# 2015_FDP_SCHEMA.net
KiCad netlist of a schematic drawn in Altium Designer
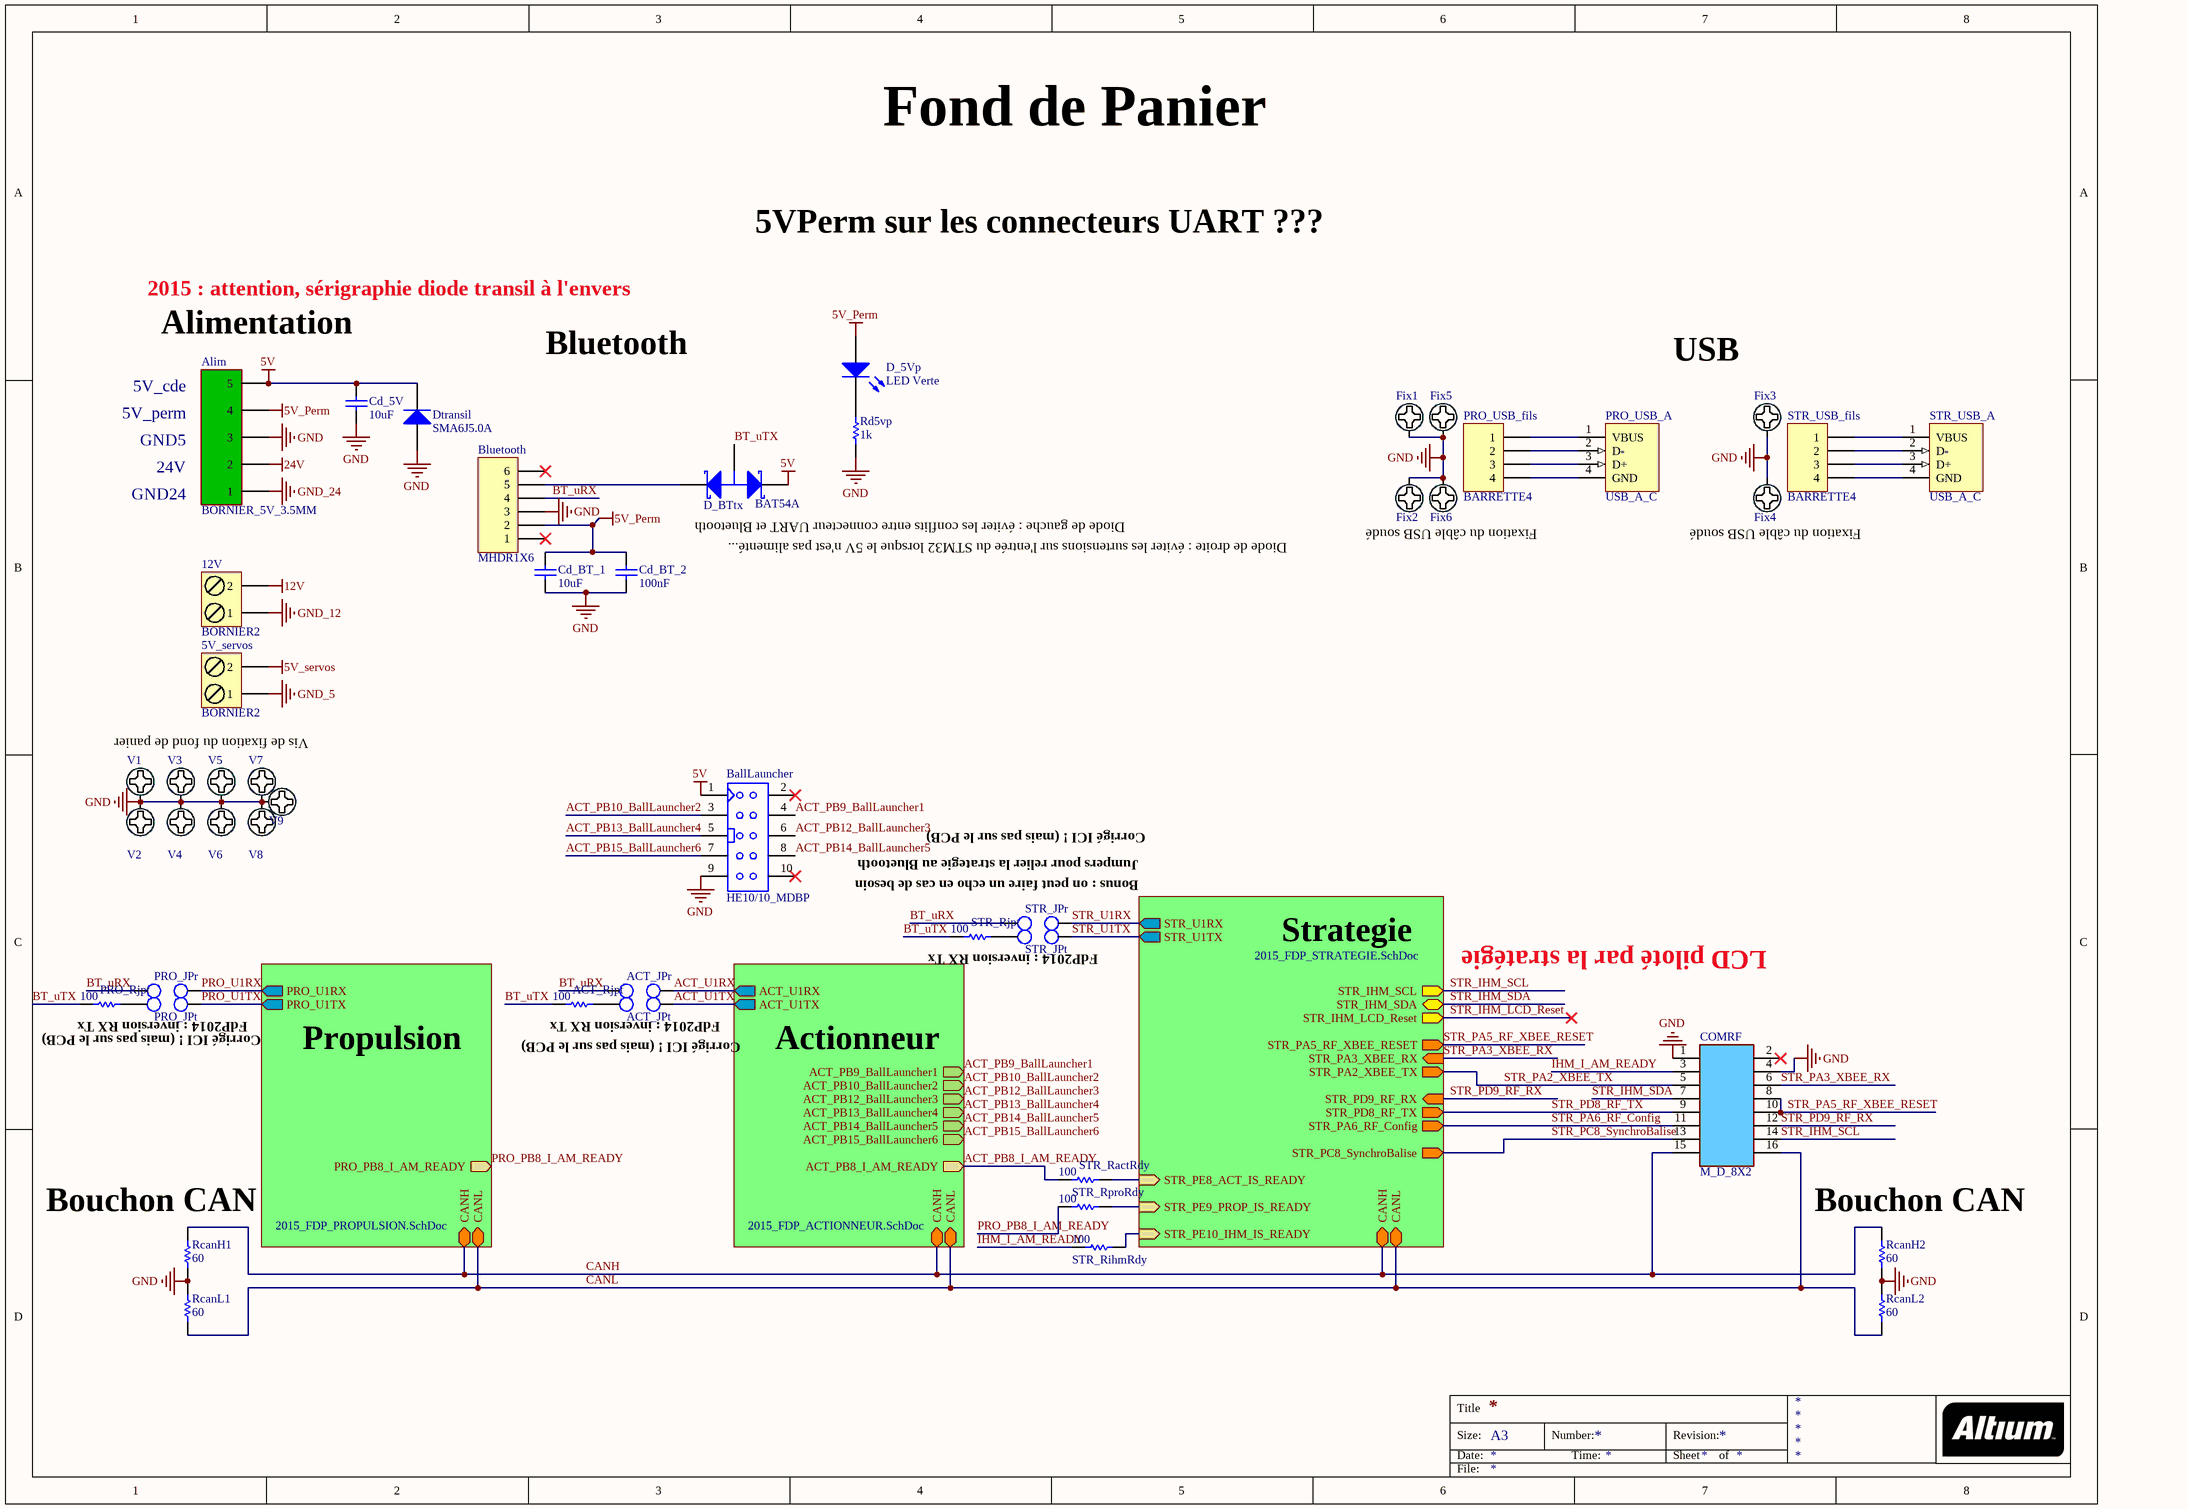
[diagram p0: 2015_FDP_SCHEMA.SchDoc]

(export (version "E")
  (design (tool "Eeschema 10.0.6"))
  (components
    (comp (ref "5V_servos")
      (value "BORNIER2")
      (footprint "BORNIER_2V_5.08MM")
      (description "Terminal blocks, 2 pins, pitch=5mm")
      (libsource (lib "Connecteur") (part "BORNIER2"))
    )
    (comp (ref "12V")
      (value "BORNIER2")
      (footprint "BORNIER_2V_5.08MM")
      (description "Terminal blocks, 2 pins, pitch=5mm")
      (libsource (lib "Connecteur") (part "BORNIER2"))
    )
    (comp (ref "ACT_JPr")
      (value "JUMPER2")
      (footprint "BARRETTE_2_M_D")
      (description "BARRETTE 2 CONTACTS 1 RANGEE MALE DROITE")
      (libsource (lib "connecteurs") (part "JUMPER2"))
    )
    (comp (ref "ACT_JPt")
      (value "JUMPER2")
      (footprint "BARRETTE_2_M_D")
      (description "BARRETTE 2 CONTACTS 1 RANGEE MALE DROITE")
      (libsource (lib "connecteurs") (part "JUMPER2"))
    )
    (comp (ref "ACT_Rjpt")
      (value "100")
      (footprint "R1206_N")
      (description "Resistor")
      (fields (field (name "PUBLISHER") "Altium Limited"))
      (libsource (lib "_ROBOT") (part "Resistor"))
    )
    (comp (ref "Alim")
      (value "BORNIER_5V_3.5MM")
      (footprint "BORNIER_5V_3.5MM_femelle_0")
      (libsource (lib "Connecteur") (part "BORNIER_5V_3.5MM"))
    )
    (comp (ref "BallLauncher")
      (value "HE10/10_MALE_DROIT_BAS_PROFIL")
      (footprint "HE10/10_M_D_BP")
      (description "EMBASE HE10/10 MALE DROIT BAS PROFIL")
      (fields (field (name "TYPE") "HE10/10_MDBP"))
      (libsource (lib "connecteurs") (part "HE10/10_MALE_DROIT_BAS_PROFIL"))
    )
    (comp (ref "Bluetooth")
      (value "MHDR1X6")
      (footprint "HE14_6")
      (description "Header, 6-Pin")
      (fields (field (name "PUBLISHER") "Altium Limited"))
      (libsource (lib "Miscellaneous Connectors") (part "MHDR1X6"))
    )
    (comp (ref "Cd_5V")
      (value "10uF")
      (footprint "C1206_N")
      (description "Capacitor")
      (fields (field (name "PUBLISHER") "Altium Limited"))
      (libsource (lib "_ROBOT") (part "Condensateur"))
    )
    (comp (ref "Cd_BT_1")
      (value "10uF")
      (footprint "C1206_N")
      (description "Capacitor")
      (fields (field (name "PUBLISHER") "Altium Limited"))
      (libsource (lib "_ROBOT") (part "Condensateur"))
    )
    (comp (ref "Cd_BT_2")
      (value "100nF")
      (footprint "C0805_N")
      (description "Capacitor")
      (fields (field (name "PUBLISHER") "Altium Limited"))
      (libsource (lib "_ROBOT") (part "Condensateur"))
    )
    (comp (ref "COMRF")
      (value "BARRETTE_8 CONTACTS_2 RANGEES_MALE_DROITE")
      (footprint "HE10/16_M_D_B P")
      (fields (field (name "TYPE") "M_D_8X2"))
      (libsource (lib "connecteurs") (part "BARRETTE_8 CONTACTS_2 RANGEES_MALE_DROITE"))
    )
    (comp (ref "Dtransil")
      (value "SMA6J5.0A")
      (footprint "DO214AC")
      (description "1 Amp General Purpose Rectifier")
      (fields (field (name "PUBLISHER") "Altium Limited"))
      (libsource (lib "Miscellaneous Devices") (part "Diode 1N4001"))
    )
    (comp (ref "D_5Vp")
      (value "LED Verte")
      (footprint "LED_0805")
      (description "Typical LED")
      (fields (field (name "PUBLISHER") "Altium Limited"))
      (libsource (lib "_ROBOT") (part "LED"))
    )
    (comp (ref "D_BTtx")
      (value "BAT54A")
      (footprint "SOT23-3N")
      (description "DIODE SCHOTTKY DOUBLE")
      (fields (field (name "MANUFACTURER") "ZETEX"))
      (libsource (lib "_ROBOT") (part "Diode Shottky double  BAT54A"))
    )
    (comp (ref "Fix1")
      (value "Pad_M3")
      (footprint "Point Test_D3_P1.6mm")
      (description "Vis M3 X 6mm _TORX_Tête 6mm")
      (fields (field (name "PUBLISHER") "Damien Guitton"))
      (libsource (lib "DG_Mecanique") (part "Vis M3 X 6mm _TORX_Tête 6mm"))
    )
    (comp (ref "Fix2")
      (value "Pad_M3")
      (footprint "Point Test_D3_P1.6mm")
      (description "Vis M3 X 6mm _TORX_Tête 6mm")
      (fields (field (name "PUBLISHER") "Damien Guitton"))
      (libsource (lib "DG_Mecanique") (part "Vis M3 X 6mm _TORX_Tête 6mm"))
    )
    (comp (ref "Fix3")
      (value "Pad_M3")
      (footprint "Point Test_D3_P1.6mm")
      (description "Vis M3 X 6mm _TORX_Tête 6mm")
      (fields (field (name "PUBLISHER") "Damien Guitton"))
      (libsource (lib "DG_Mecanique") (part "Vis M3 X 6mm _TORX_Tête 6mm"))
    )
    (comp (ref "Fix4")
      (value "Pad_M3")
      (footprint "Point Test_D3_P1.6mm")
      (description "Vis M3 X 6mm _TORX_Tête 6mm")
      (fields (field (name "PUBLISHER") "Damien Guitton"))
      (libsource (lib "DG_Mecanique") (part "Vis M3 X 6mm _TORX_Tête 6mm"))
    )
    (comp (ref "Fix5")
      (value "Pad_M3")
      (footprint "Point Test_D3_P1.6mm")
      (description "Vis M3 X 6mm _TORX_Tête 6mm")
      (fields (field (name "PUBLISHER") "Damien Guitton"))
      (libsource (lib "DG_Mecanique") (part "Vis M3 X 6mm _TORX_Tête 6mm"))
    )
    (comp (ref "Fix6")
      (value "Pad_M3")
      (footprint "Point Test_D3_P1.6mm")
      (description "Vis M3 X 6mm _TORX_Tête 6mm")
      (fields (field (name "PUBLISHER") "Damien Guitton"))
      (libsource (lib "DG_Mecanique") (part "Vis M3 X 6mm _TORX_Tête 6mm"))
    )
    (comp (ref "PRO_JPr")
      (value "JUMPER2")
      (footprint "BARRETTE_2_M_D")
      (description "BARRETTE 2 CONTACTS 1 RANGEE MALE DROITE")
      (libsource (lib "connecteurs") (part "JUMPER2"))
    )
    (comp (ref "PRO_JPt")
      (value "JUMPER2")
      (footprint "BARRETTE_2_M_D")
      (description "BARRETTE 2 CONTACTS 1 RANGEE MALE DROITE")
      (libsource (lib "connecteurs") (part "JUMPER2"))
    )
    (comp (ref "PRO_Rjpt")
      (value "100")
      (footprint "R1206_N")
      (description "Resistor")
      (fields (field (name "PUBLISHER") "Altium Limited"))
      (libsource (lib "_ROBOT") (part "Resistor"))
    )
    (comp (ref "PRO_USB_A")
      (value "USB_A_COUDEE")
      (footprint "USB_A_C")
      (description "EMBASE USB TRAVERSANTE TYPE A COUDEE")
      (fields (field (name "TYPE") "USB_A_C"))
      (libsource (lib "connecteurs") (part "USB_A_COUDEE"))
    )
    (comp (ref "PRO_USB_fils")
      (value "BARRETTE4")
      (footprint "HE14_4")
      (description "Header, 4-Pin")
      (fields (field (name "PUBLISHER") "Altium Limited"))
      (libsource (lib "Connecteur") (part "BARRETTE4"))
    )
    (comp (ref "RcanH1")
      (value "60")
      (footprint "R1206_N")
      (description "Resistor")
      (fields (field (name "PUBLISHER") "Altium Limited"))
      (libsource (lib "_ROBOT") (part "Resistor"))
    )
    (comp (ref "RcanH2")
      (value "60")
      (footprint "R1206_N")
      (description "Resistor")
      (fields (field (name "PUBLISHER") "Altium Limited"))
      (libsource (lib "_ROBOT") (part "Resistor"))
    )
    (comp (ref "RcanL1")
      (value "60")
      (footprint "R1206_N")
      (description "Resistor")
      (fields (field (name "PUBLISHER") "Altium Limited"))
      (libsource (lib "_ROBOT") (part "Resistor"))
    )
    (comp (ref "RcanL2")
      (value "60")
      (footprint "R1206_N")
      (description "Resistor")
      (fields (field (name "PUBLISHER") "Altium Limited"))
      (libsource (lib "_ROBOT") (part "Resistor"))
    )
    (comp (ref "Rd5vp")
      (value "1k")
      (footprint "R1206_N")
      (description "Resistor")
      (fields (field (name "PUBLISHER") "Altium Limited"))
      (libsource (lib "_ROBOT") (part "Resistor"))
    )
    (comp (ref "STR_JPr")
      (value "JUMPER2")
      (footprint "BARRETTE_2_M_D")
      (description "BARRETTE 2 CONTACTS 1 RANGEE MALE DROITE")
      (libsource (lib "connecteurs") (part "JUMPER2"))
    )
    (comp (ref "STR_JPt")
      (value "JUMPER2")
      (footprint "BARRETTE_2_M_D")
      (description "BARRETTE 2 CONTACTS 1 RANGEE MALE DROITE")
      (libsource (lib "connecteurs") (part "JUMPER2"))
    )
    (comp (ref "STR_RactRdy")
      (value "100")
      (footprint "R1206_N")
      (description "Resistor")
      (fields (field (name "PUBLISHER") "Altium Limited"))
      (libsource (lib "_ROBOT") (part "Resistor"))
    )
    (comp (ref "STR_RihmRdy")
      (value "100")
      (footprint "R1206_N")
      (description "Resistor")
      (fields (field (name "PUBLISHER") "Altium Limited"))
      (libsource (lib "_ROBOT") (part "Resistor"))
    )
    (comp (ref "STR_Rjpt")
      (value "100")
      (footprint "R1206_N")
      (description "Resistor")
      (fields (field (name "PUBLISHER") "Altium Limited"))
      (libsource (lib "_ROBOT") (part "Resistor"))
    )
    (comp (ref "STR_RproRdy")
      (value "100")
      (footprint "R1206_N")
      (description "Resistor")
      (fields (field (name "PUBLISHER") "Altium Limited"))
      (libsource (lib "_ROBOT") (part "Resistor"))
    )
    (comp (ref "STR_USB_A")
      (value "USB_A_COUDEE")
      (footprint "USB_A_C")
      (description "EMBASE USB TRAVERSANTE TYPE A COUDEE")
      (fields (field (name "TYPE") "USB_A_C"))
      (libsource (lib "connecteurs") (part "USB_A_COUDEE"))
    )
    (comp (ref "STR_USB_fils")
      (value "BARRETTE4")
      (footprint "HE14_4")
      (description "Header, 4-Pin")
      (fields (field (name "PUBLISHER") "Altium Limited"))
      (libsource (lib "Connecteur") (part "BARRETTE4"))
    )
    (comp (ref "V1")
      (value "Pad_M3")
      (footprint "M3x6mm Torx")
      (description "Vis M3 X 6mm _TORX_Tête 6mm")
      (fields (field (name "PUBLISHER") "Damien Guitton"))
      (libsource (lib "DG_Mecanique") (part "Vis M3 X 6mm _TORX_Tête 6mm"))
    )
    (comp (ref "V2")
      (value "Pad_M3")
      (footprint "M3x6mm Torx")
      (description "Vis M3 X 6mm _TORX_Tête 6mm")
      (fields (field (name "PUBLISHER") "Damien Guitton"))
      (libsource (lib "DG_Mecanique") (part "Vis M3 X 6mm _TORX_Tête 6mm"))
    )
    (comp (ref "V3")
      (value "Pad_M3")
      (footprint "M3x6mm Torx")
      (description "Vis M3 X 6mm _TORX_Tête 6mm")
      (fields (field (name "PUBLISHER") "Damien Guitton"))
      (libsource (lib "DG_Mecanique") (part "Vis M3 X 6mm _TORX_Tête 6mm"))
    )
    (comp (ref "V4")
      (value "Pad_M3")
      (footprint "M3x6mm Torx")
      (description "Vis M3 X 6mm _TORX_Tête 6mm")
      (fields (field (name "PUBLISHER") "Damien Guitton"))
      (libsource (lib "DG_Mecanique") (part "Vis M3 X 6mm _TORX_Tête 6mm"))
    )
    (comp (ref "V5")
      (value "Pad_M3")
      (footprint "M3x6mm Torx")
      (description "Vis M3 X 6mm _TORX_Tête 6mm")
      (fields (field (name "PUBLISHER") "Damien Guitton"))
      (libsource (lib "DG_Mecanique") (part "Vis M3 X 6mm _TORX_Tête 6mm"))
    )
    (comp (ref "V6")
      (value "Pad_M3")
      (footprint "M3x6mm Torx")
      (description "Vis M3 X 6mm _TORX_Tête 6mm")
      (fields (field (name "PUBLISHER") "Damien Guitton"))
      (libsource (lib "DG_Mecanique") (part "Vis M3 X 6mm _TORX_Tête 6mm"))
    )
    (comp (ref "V7")
      (value "Pad_M3")
      (footprint "M3x6mm Torx")
      (description "Vis M3 X 6mm _TORX_Tête 6mm")
      (fields (field (name "PUBLISHER") "Damien Guitton"))
      (libsource (lib "DG_Mecanique") (part "Vis M3 X 6mm _TORX_Tête 6mm"))
    )
    (comp (ref "V8")
      (value "Pad_M3")
      (footprint "M3x6mm Torx")
      (description "Vis M3 X 6mm _TORX_Tête 6mm")
      (fields (field (name "PUBLISHER") "Damien Guitton"))
      (libsource (lib "DG_Mecanique") (part "Vis M3 X 6mm _TORX_Tête 6mm"))
    )
    (comp (ref "V9")
      (value "Pad_M3")
      (footprint "M3x6mm Torx")
      (description "Vis M3 X 6mm _TORX_Tête 6mm")
      (fields (field (name "PUBLISHER") "Damien Guitton"))
      (libsource (lib "DG_Mecanique") (part "Vis M3 X 6mm _TORX_Tête 6mm"))
    )
  )
  (nets
    (net (code "1") (name "/ACT_PB8_I_AM_READY") (class "Default")
      (node (ref "STR_RactRdy") (pin "2") (pinfunction "2_2") (pintype "passive"))
    )
    (net (code "2") (name "/ACT_PB9_BallLauncher1") (class "Default")
      (node (ref "BallLauncher") (pin "4") (pinfunction "4_4") (pintype "passive"))
    )
    (net (code "3") (name "/ACT_PB10_BallLauncher2") (class "Default")
      (node (ref "BallLauncher") (pin "3") (pinfunction "3_3") (pintype "passive"))
    )
    (net (code "4") (name "/ACT_PB12_BallLauncher3") (class "Default")
      (node (ref "BallLauncher") (pin "6") (pinfunction "6_6") (pintype "passive"))
    )
    (net (code "5") (name "/ACT_PB13_BallLauncher4") (class "Default")
      (node (ref "BallLauncher") (pin "5") (pinfunction "5_5") (pintype "passive"))
    )
    (net (code "6") (name "/ACT_PB14_BallLauncher5") (class "Default")
      (node (ref "BallLauncher") (pin "8") (pinfunction "8_8") (pintype "passive"))
    )
    (net (code "7") (name "/ACT_PB15_BallLauncher6") (class "Default")
      (node (ref "BallLauncher") (pin "7") (pinfunction "7_7") (pintype "passive"))
    )
    (net (code "8") (name "/ACT_U1RX") (class "Default")
      (node (ref "ACT_JPr") (pin "2") (pinfunction "2_2") (pintype "passive"))
    )
    (net (code "9") (name "/ACT_U1TX") (class "Default")
      (node (ref "ACT_JPt") (pin "2") (pinfunction "2_2") (pintype "passive"))
    )
    (net (code "10") (name "/BT_uRX") (class "Default")
      (node (ref "ACT_JPr") (pin "1") (pinfunction "1_1") (pintype "passive"))
      (node (ref "Bluetooth") (pin "4") (pinfunction "4_4") (pintype "passive"))
      (node (ref "PRO_JPr") (pin "1") (pinfunction "1_1") (pintype "passive"))
      (node (ref "STR_JPr") (pin "1") (pinfunction "1_1") (pintype "passive"))
    )
    (net (code "11") (name "/BT_uTX") (class "Default")
      (node (ref "ACT_Rjpt") (pin "2") (pinfunction "2_2") (pintype "passive"))
      (node (ref "D_BTtx") (pin "3") (pinfunction "A_3") (pintype "passive"))
      (node (ref "PRO_Rjpt") (pin "2") (pinfunction "2_2") (pintype "passive"))
      (node (ref "STR_Rjpt") (pin "2") (pinfunction "2_2") (pintype "passive"))
    )
    (net (code "12") (name "/CANH") (class "Default")
      (node (ref "COMRF") (pin "15") (pinfunction "15_15") (pintype "passive"))
      (node (ref "RcanH1") (pin "2") (pinfunction "2_2") (pintype "passive"))
      (node (ref "RcanH2") (pin "1") (pinfunction "1_1") (pintype "passive"))
    )
    (net (code "13") (name "/CANL") (class "Default")
      (node (ref "COMRF") (pin "16") (pinfunction "16_16") (pintype "passive"))
      (node (ref "RcanL1") (pin "1") (pinfunction "1_1") (pintype "passive"))
      (node (ref "RcanL2") (pin "1") (pinfunction "1_1") (pintype "passive"))
    )
    (net (code "14") (name "/IHM_I_AM_READY") (class "Default")
      (node (ref "COMRF") (pin "3") (pinfunction "3_3") (pintype "passive"))
      (node (ref "STR_RihmRdy") (pin "2") (pinfunction "2_2") (pintype "passive"))
    )
    (net (code "15") (name "/PRO_PB8_I_AM_READY") (class "Default")
      (node (ref "STR_RproRdy") (pin "2") (pinfunction "2_2") (pintype "passive"))
    )
    (net (code "16") (name "/PRO_U1RX") (class "Default")
      (node (ref "PRO_JPr") (pin "2") (pinfunction "2_2") (pintype "passive"))
    )
    (net (code "17") (name "/PRO_U1TX") (class "Default")
      (node (ref "PRO_JPt") (pin "2") (pinfunction "2_2") (pintype "passive"))
    )
    (net (code "19") (name "/STR_IHM_SCL") (class "Default")
      (node (ref "COMRF") (pin "14") (pinfunction "14_14") (pintype "passive"))
    )
    (net (code "20") (name "/STR_IHM_SDA") (class "Default")
      (node (ref "COMRF") (pin "7") (pinfunction "7_7") (pintype "passive"))
    )
    (net (code "21") (name "/STR_PA2_XBEE_TX") (class "Default")
      (node (ref "COMRF") (pin "5") (pinfunction "5_5") (pintype "passive"))
    )
    (net (code "22") (name "/STR_PA3_XBEE_RX") (class "Default")
      (node (ref "COMRF") (pin "6") (pinfunction "6_6") (pintype "passive"))
    )
    (net (code "23") (name "/STR_PA5_RF_XBEE_RESET") (class "Default")
      (node (ref "COMRF") (pin "10") (pinfunction "10_10") (pintype "passive"))
      (node (ref "COMRF") (pin "8") (pinfunction "8_8") (pintype "passive"))
    )
    (net (code "24") (name "/STR_PA6_RF_Config") (class "Default")
      (node (ref "COMRF") (pin "11") (pinfunction "11_11") (pintype "passive"))
    )
    (net (code "25") (name "/STR_PC8_SynchroBalise") (class "Default")
      (node (ref "COMRF") (pin "13") (pinfunction "13_13") (pintype "passive"))
    )
    (net (code "26") (name "/STR_PD8_RF_TX") (class "Default")
      (node (ref "COMRF") (pin "9") (pinfunction "9_9") (pintype "passive"))
    )
    (net (code "27") (name "/STR_PD9_RF_RX") (class "Default")
      (node (ref "COMRF") (pin "12") (pinfunction "12_12") (pintype "passive"))
    )
    (net (code "28") (name "/STR_PE8_ACT_IS_READY") (class "Default")
      (node (ref "STR_RactRdy") (pin "1") (pinfunction "1_1") (pintype "passive"))
    )
    (net (code "29") (name "/STR_PE9_PROP_IS_READY") (class "Default")
      (node (ref "STR_RproRdy") (pin "1") (pinfunction "1_1") (pintype "passive"))
    )
    (net (code "30") (name "/STR_PE10_IHM_IS_READY") (class "Default")
      (node (ref "STR_RihmRdy") (pin "1") (pinfunction "1_1") (pintype "passive"))
    )
    (net (code "31") (name "/STR_U1RX") (class "Default")
      (node (ref "STR_JPr") (pin "2") (pinfunction "2_2") (pintype "passive"))
    )
    (net (code "32") (name "/STR_U1TX") (class "Default")
      (node (ref "STR_JPt") (pin "2") (pinfunction "2_2") (pintype "passive"))
    )
    (net (code "33") (name "5V") (class "Default")
      (node (ref "Alim") (pin "5") (pinfunction "5_5") (pintype "passive"))
      (node (ref "BallLauncher") (pin "1") (pinfunction "1_1") (pintype "passive"))
      (node (ref "Cd_5V") (pin "2") (pinfunction "2_2") (pintype "passive"))
      (node (ref "D_BTtx") (pin "2") (pinfunction "K2_2") (pintype "passive"))
      (node (ref "Dtransil") (pin "2") (pinfunction "K_2") (pintype "passive"))
    )
    (net (code "34") (name "5V_Perm") (class "Default")
      (node (ref "Alim") (pin "4") (pinfunction "4_4") (pintype "passive"))
      (node (ref "Bluetooth") (pin "2") (pinfunction "2_2") (pintype "passive"))
      (node (ref "Cd_BT_1") (pin "2") (pinfunction "2_2") (pintype "passive"))
      (node (ref "Cd_BT_2") (pin "2") (pinfunction "2_2") (pintype "passive"))
      (node (ref "D_5Vp") (pin "1") (pinfunction "A_1") (pintype "passive"))
    )
    (net (code "35") (name "5V_servos") (class "Default")
      (node (ref "5V_servos") (pin "2") (pinfunction "2_2") (pintype "passive"))
    )
    (net (code "36") (name "12V") (class "Default")
      (node (ref "12V") (pin "2") (pinfunction "2_2") (pintype "passive"))
    )
    (net (code "37") (name "24V") (class "Default")
      (node (ref "Alim") (pin "2") (pinfunction "2_2") (pintype "passive"))
    )
    (net (code "38") (name "GND") (class "Default")
      (node (ref "Alim") (pin "3") (pinfunction "3_3") (pintype "passive"))
      (node (ref "BallLauncher") (pin "9") (pinfunction "9_9") (pintype "passive"))
      (node (ref "Bluetooth") (pin "3") (pinfunction "3_3") (pintype "passive"))
      (node (ref "COMRF") (pin "1") (pinfunction "1_1") (pintype "passive"))
      (node (ref "COMRF") (pin "4") (pinfunction "4_4") (pintype "passive"))
      (node (ref "Cd_5V") (pin "1") (pinfunction "1_1") (pintype "passive"))
      (node (ref "Cd_BT_1") (pin "1") (pinfunction "1_1") (pintype "passive"))
      (node (ref "Cd_BT_2") (pin "1") (pinfunction "1_1") (pintype "passive"))
      (node (ref "Dtransil") (pin "1") (pinfunction "A_1") (pintype "passive"))
      (node (ref "Fix1") (pin "1") (pinfunction "1_1") (pintype "passive"))
      (node (ref "Fix2") (pin "1") (pinfunction "1_1") (pintype "passive"))
      (node (ref "Fix3") (pin "1") (pinfunction "1_1") (pintype "passive"))
      (node (ref "Fix4") (pin "1") (pinfunction "1_1") (pintype "passive"))
      (node (ref "Fix5") (pin "1") (pinfunction "1_1") (pintype "passive"))
      (node (ref "Fix6") (pin "1") (pinfunction "1_1") (pintype "passive"))
      (node (ref "RcanH1") (pin "1") (pinfunction "1_1") (pintype "passive"))
      (node (ref "RcanH2") (pin "2") (pinfunction "2_2") (pintype "passive"))
      (node (ref "RcanL1") (pin "2") (pinfunction "2_2") (pintype "passive"))
      (node (ref "RcanL2") (pin "2") (pinfunction "2_2") (pintype "passive"))
      (node (ref "Rd5vp") (pin "2") (pinfunction "2_2") (pintype "passive"))
      (node (ref "V1") (pin "1") (pinfunction "1_1") (pintype "passive"))
      (node (ref "V2") (pin "1") (pinfunction "1_1") (pintype "passive"))
      (node (ref "V3") (pin "1") (pinfunction "1_1") (pintype "passive"))
      (node (ref "V4") (pin "1") (pinfunction "1_1") (pintype "passive"))
      (node (ref "V5") (pin "1") (pinfunction "1_1") (pintype "passive"))
      (node (ref "V6") (pin "1") (pinfunction "1_1") (pintype "passive"))
      (node (ref "V7") (pin "1") (pinfunction "1_1") (pintype "passive"))
      (node (ref "V8") (pin "1") (pinfunction "1_1") (pintype "passive"))
      (node (ref "V9") (pin "1") (pinfunction "1_1") (pintype "passive"))
    )
    (net (code "39") (name "GND_5") (class "Default")
      (node (ref "5V_servos") (pin "1") (pinfunction "1_1") (pintype "passive"))
    )
    (net (code "40") (name "GND_12") (class "Default")
      (node (ref "12V") (pin "1") (pinfunction "1_1") (pintype "passive"))
    )
    (net (code "41") (name "GND_24") (class "Default")
      (node (ref "Alim") (pin "1") (pinfunction "1_1") (pintype "passive"))
    )
    (net (code "42") (name "Net-(ACT_JPt-Pad1)") (class "Default")
      (node (ref "ACT_JPt") (pin "1") (pinfunction "1_1") (pintype "passive"))
      (node (ref "ACT_Rjpt") (pin "1") (pinfunction "1_1") (pintype "passive"))
    )
    (net (code "43") (name "Net-(D_5Vp-K)") (class "Default")
      (node (ref "D_5Vp") (pin "2") (pinfunction "K_2") (pintype "passive"))
      (node (ref "Rd5vp") (pin "1") (pinfunction "1_1") (pintype "passive"))
    )
    (net (code "44") (name "Net-(D_BTtx-K1)") (class "Default")
      (node (ref "Bluetooth") (pin "5") (pinfunction "5_5") (pintype "passive"))
      (node (ref "D_BTtx") (pin "1") (pinfunction "K1_1") (pintype "passive"))
    )
    (net (code "45") (name "Net-(PRO_JPt-Pad1)") (class "Default")
      (node (ref "PRO_JPt") (pin "1") (pinfunction "1_1") (pintype "passive"))
      (node (ref "PRO_Rjpt") (pin "1") (pinfunction "1_1") (pintype "passive"))
    )
    (net (code "46") (name "Net-(PRO_USB_A-D+)") (class "Default")
      (node (ref "PRO_USB_A") (pin "3") (pinfunction "D+_3") (pintype "input"))
      (node (ref "PRO_USB_fils") (pin "3") (pinfunction "3_3") (pintype "passive"))
    )
    (net (code "47") (name "Net-(PRO_USB_A-D-)") (class "Default")
      (node (ref "PRO_USB_A") (pin "2") (pinfunction "D-_2") (pintype "input"))
      (node (ref "PRO_USB_fils") (pin "2") (pinfunction "2_2") (pintype "passive"))
    )
    (net (code "48") (name "Net-(PRO_USB_A-GND)") (class "Default")
      (node (ref "PRO_USB_A") (pin "4") (pinfunction "GND_4") (pintype "power_in"))
      (node (ref "PRO_USB_fils") (pin "4") (pinfunction "4_4") (pintype "passive"))
    )
    (net (code "49") (name "Net-(PRO_USB_A-VBUS)") (class "Default")
      (node (ref "PRO_USB_A") (pin "1") (pinfunction "VBUS_1") (pintype "power_in"))
      (node (ref "PRO_USB_fils") (pin "1") (pinfunction "1_1") (pintype "passive"))
    )
    (net (code "50") (name "Net-(STR_JPt-Pad1)") (class "Default")
      (node (ref "STR_JPt") (pin "1") (pinfunction "1_1") (pintype "passive"))
      (node (ref "STR_Rjpt") (pin "1") (pinfunction "1_1") (pintype "passive"))
    )
    (net (code "51") (name "Net-(STR_USB_A-D+)") (class "Default")
      (node (ref "STR_USB_A") (pin "3") (pinfunction "D+_3") (pintype "input"))
      (node (ref "STR_USB_fils") (pin "3") (pinfunction "3_3") (pintype "passive"))
    )
    (net (code "52") (name "Net-(STR_USB_A-D-)") (class "Default")
      (node (ref "STR_USB_A") (pin "2") (pinfunction "D-_2") (pintype "input"))
      (node (ref "STR_USB_fils") (pin "2") (pinfunction "2_2") (pintype "passive"))
    )
    (net (code "53") (name "Net-(STR_USB_A-GND)") (class "Default")
      (node (ref "STR_USB_A") (pin "4") (pinfunction "GND_4") (pintype "power_in"))
      (node (ref "STR_USB_fils") (pin "4") (pinfunction "4_4") (pintype "passive"))
    )
    (net (code "54") (name "Net-(STR_USB_A-VBUS)") (class "Default")
      (node (ref "STR_USB_A") (pin "1") (pinfunction "VBUS_1") (pintype "power_in"))
      (node (ref "STR_USB_fils") (pin "1") (pinfunction "1_1") (pintype "passive"))
    )
    (net (code "55") (name "unconnected-(BallLauncher-Pad2)") (class "Default")
      (node (ref "BallLauncher") (pin "2") (pinfunction "2_2") (pintype "passive+no_connect"))
    )
    (net (code "56") (name "unconnected-(BallLauncher-Pad10)") (class "Default")
      (node (ref "BallLauncher") (pin "10") (pinfunction "10_10") (pintype "passive+no_connect"))
    )
    (net (code "57") (name "unconnected-(Bluetooth-Pad1)") (class "Default")
      (node (ref "Bluetooth") (pin "1") (pinfunction "1_1") (pintype "passive+no_connect"))
    )
    (net (code "58") (name "unconnected-(Bluetooth-Pad6)") (class "Default")
      (node (ref "Bluetooth") (pin "6") (pinfunction "6_6") (pintype "passive+no_connect"))
    )
    (net (code "59") (name "unconnected-(COMRF-Pad2)") (class "Default")
      (node (ref "COMRF") (pin "2") (pinfunction "2_2") (pintype "passive+no_connect"))
    )
  )
)
